# Circuit_Set_1.net
KiCad netlist of a schematic drawn in EAGLE
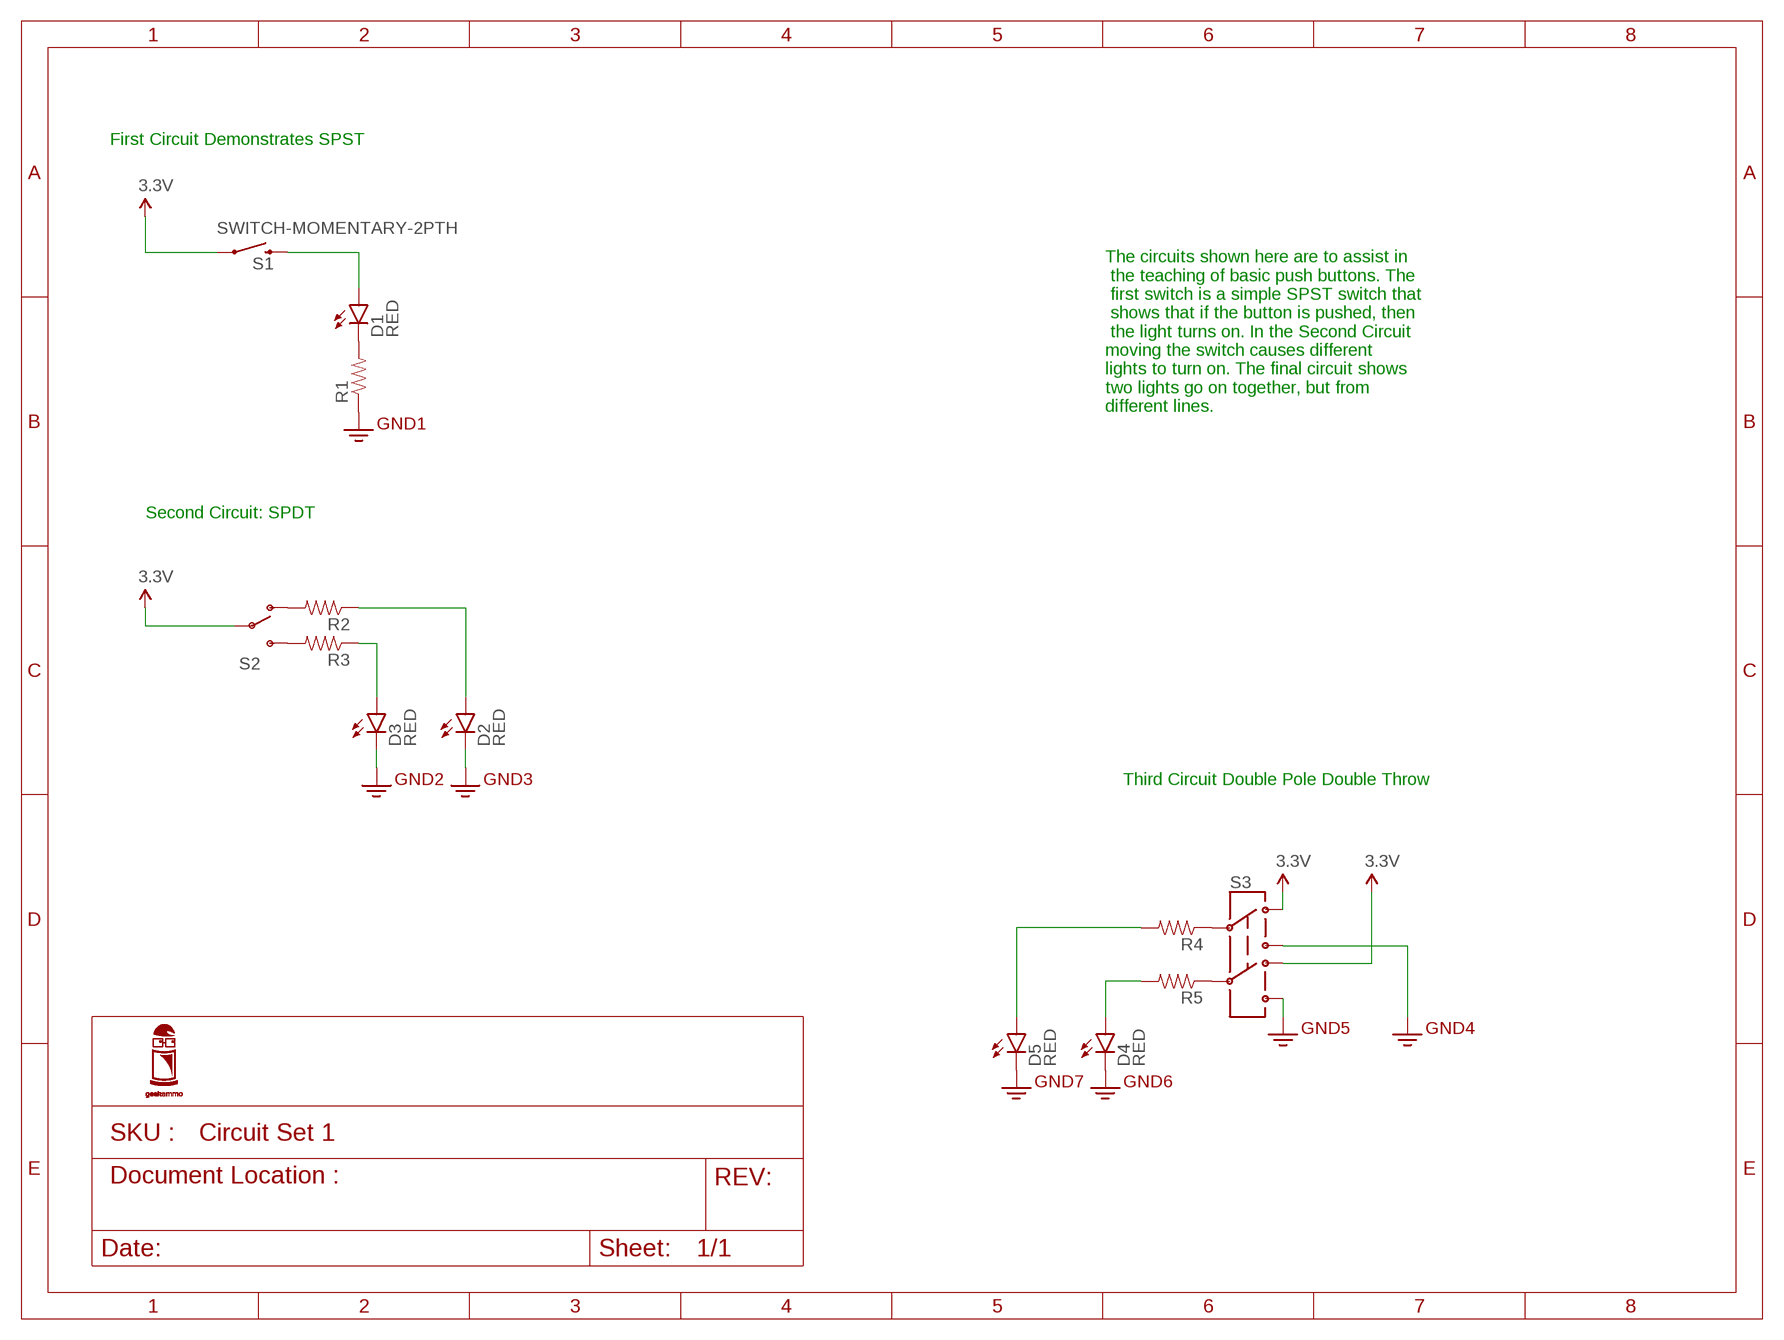
[diagram p0: schematic, sheet 1]

(export (version "E")
  (design (tool "Eeschema 10.0.6"))
  (components
    (comp (ref "D1")
      (value "RED")
      (footprint "eagle-import:LED-0603")
      (libsource (lib "eagle-import") (part "LED-RED0603"))
    )
    (comp (ref "D2")
      (value "RED")
      (footprint "eagle-import:LED-0603")
      (libsource (lib "eagle-import") (part "LED-RED0603"))
    )
    (comp (ref "D3")
      (value "RED")
      (footprint "eagle-import:LED-0603")
      (libsource (lib "eagle-import") (part "LED-RED0603"))
    )
    (comp (ref "D4")
      (value "RED")
      (footprint "eagle-import:LED-0603")
      (libsource (lib "eagle-import") (part "LED-RED0603"))
    )
    (comp (ref "D5")
      (value "RED")
      (footprint "eagle-import:LED-0603")
      (libsource (lib "eagle-import") (part "LED-RED0603"))
    )
    (comp (ref "R1")
      (value "RESISTOR0805-RES")
      (footprint "eagle-import:0805")
      (libsource (lib "eagle-import") (part "RESISTOR0805-RES"))
    )
    (comp (ref "R2")
      (value "RESISTOR0805-RES")
      (footprint "eagle-import:0805")
      (libsource (lib "eagle-import") (part "RESISTOR0805-RES"))
    )
    (comp (ref "R3")
      (value "RESISTOR0805-RES")
      (footprint "eagle-import:0805")
      (libsource (lib "eagle-import") (part "RESISTOR0805-RES"))
    )
    (comp (ref "R4")
      (value "RESISTOR0805-RES")
      (footprint "eagle-import:0805")
      (libsource (lib "eagle-import") (part "RESISTOR0805-RES"))
    )
    (comp (ref "R5")
      (value "RESISTOR0805-RES")
      (footprint "eagle-import:0805")
      (libsource (lib "eagle-import") (part "RESISTOR0805-RES"))
    )
    (comp (ref "S1")
      (value "SWITCH-MOMENTARY-2PTH")
      (footprint "eagle-import:TACTILE-PTH")
      (libsource (lib "eagle-import") (part "SWITCH-MOMENTARY-2PTH"))
    )
    (comp (ref "S2")
      (value "SWITCH-SPDTKIT")
      (footprint "eagle-import:SWITCH-SPDT_KIT")
      (libsource (lib "eagle-import") (part "SWITCH-SPDTKIT"))
    )
    (comp (ref "S3")
      (value "SWITCH-DPDTES")
      (footprint "eagle-import:ES")
      (libsource (lib "eagle-import") (part "SWITCH-DPDTES"))
    )
  )
  (nets
    (net (code "1") (name "3.3V") (class "Default")
      (node (ref "D2") (pin "C") (pinfunction "C_C") (pintype "passive"))
      (node (ref "D3") (pin "C") (pinfunction "C_C") (pintype "passive"))
      (node (ref "D4") (pin "C") (pinfunction "C_C") (pintype "passive"))
      (node (ref "D5") (pin "C") (pinfunction "C_C") (pintype "passive"))
      (node (ref "R1") (pin "1") (pinfunction "1_1") (pintype "passive"))
      (node (ref "S1") (pin "1") (pinfunction "1_1") (pintype "passive"))
      (node (ref "S2") (pin "2") (pinfunction "P_2") (pintype "passive"))
      (node (ref "S3") (pin "1") (pinfunction "1_1") (pintype "bidirectional"))
      (node (ref "S3") (pin "3") (pinfunction "3_3") (pintype "bidirectional"))
      (node (ref "S3") (pin "4") (pinfunction "4_4") (pintype "bidirectional"))
      (node (ref "S3") (pin "6") (pinfunction "6_6") (pintype "bidirectional"))
    )
    (net (code "2") (name "Net-(D1-PadC)") (class "Default")
      (node (ref "D1") (pin "C") (pinfunction "C_C") (pintype "passive"))
      (node (ref "R1") (pin "2") (pinfunction "2_2") (pintype "passive"))
    )
    (net (code "3") (name "Net-(D2-PadA)") (class "Default")
      (node (ref "D2") (pin "A") (pinfunction "A_A") (pintype "passive"))
      (node (ref "R2") (pin "1") (pinfunction "1_1") (pintype "passive"))
    )
    (net (code "4") (name "Net-(D3-PadA)") (class "Default")
      (node (ref "D3") (pin "A") (pinfunction "A_A") (pintype "passive"))
      (node (ref "R3") (pin "1") (pinfunction "1_1") (pintype "passive"))
    )
    (net (code "5") (name "Net-(D4-PadA)") (class "Default")
      (node (ref "D4") (pin "A") (pinfunction "A_A") (pintype "passive"))
      (node (ref "R5") (pin "2") (pinfunction "2_2") (pintype "passive"))
    )
    (net (code "6") (name "Net-(D5-PadA)") (class "Default")
      (node (ref "D5") (pin "A") (pinfunction "A_A") (pintype "passive"))
      (node (ref "R4") (pin "2") (pinfunction "2_2") (pintype "passive"))
    )
    (net (code "7") (name "Net-(R4-Pad1)") (class "Default")
      (node (ref "R4") (pin "1") (pinfunction "1_1") (pintype "passive"))
      (node (ref "S3") (pin "2") (pinfunction "2_2") (pintype "bidirectional"))
    )
    (net (code "8") (name "Net-(R5-Pad1)") (class "Default")
      (node (ref "R5") (pin "1") (pinfunction "1_1") (pintype "passive"))
      (node (ref "S3") (pin "5") (pinfunction "5_5") (pintype "bidirectional"))
    )
    (net (code "9") (name "Net-(S1-2)") (class "Default")
      (node (ref "D1") (pin "A") (pinfunction "A_A") (pintype "passive"))
      (node (ref "S1") (pin "3") (pinfunction "2_3") (pintype "passive"))
    )
    (net (code "10") (name "Net-(S2-O)") (class "Default")
      (node (ref "R2") (pin "2") (pinfunction "2_2") (pintype "passive"))
      (node (ref "S2") (pin "1") (pinfunction "O_1") (pintype "passive"))
    )
    (net (code "11") (name "Net-(S2-S)") (class "Default")
      (node (ref "R3") (pin "2") (pinfunction "2_2") (pintype "passive"))
      (node (ref "S2") (pin "3") (pinfunction "S_3") (pintype "passive"))
    )
  )
)
